# PIC32MZ.net
KiCad netlist of a schematic drawn in Altium Designer
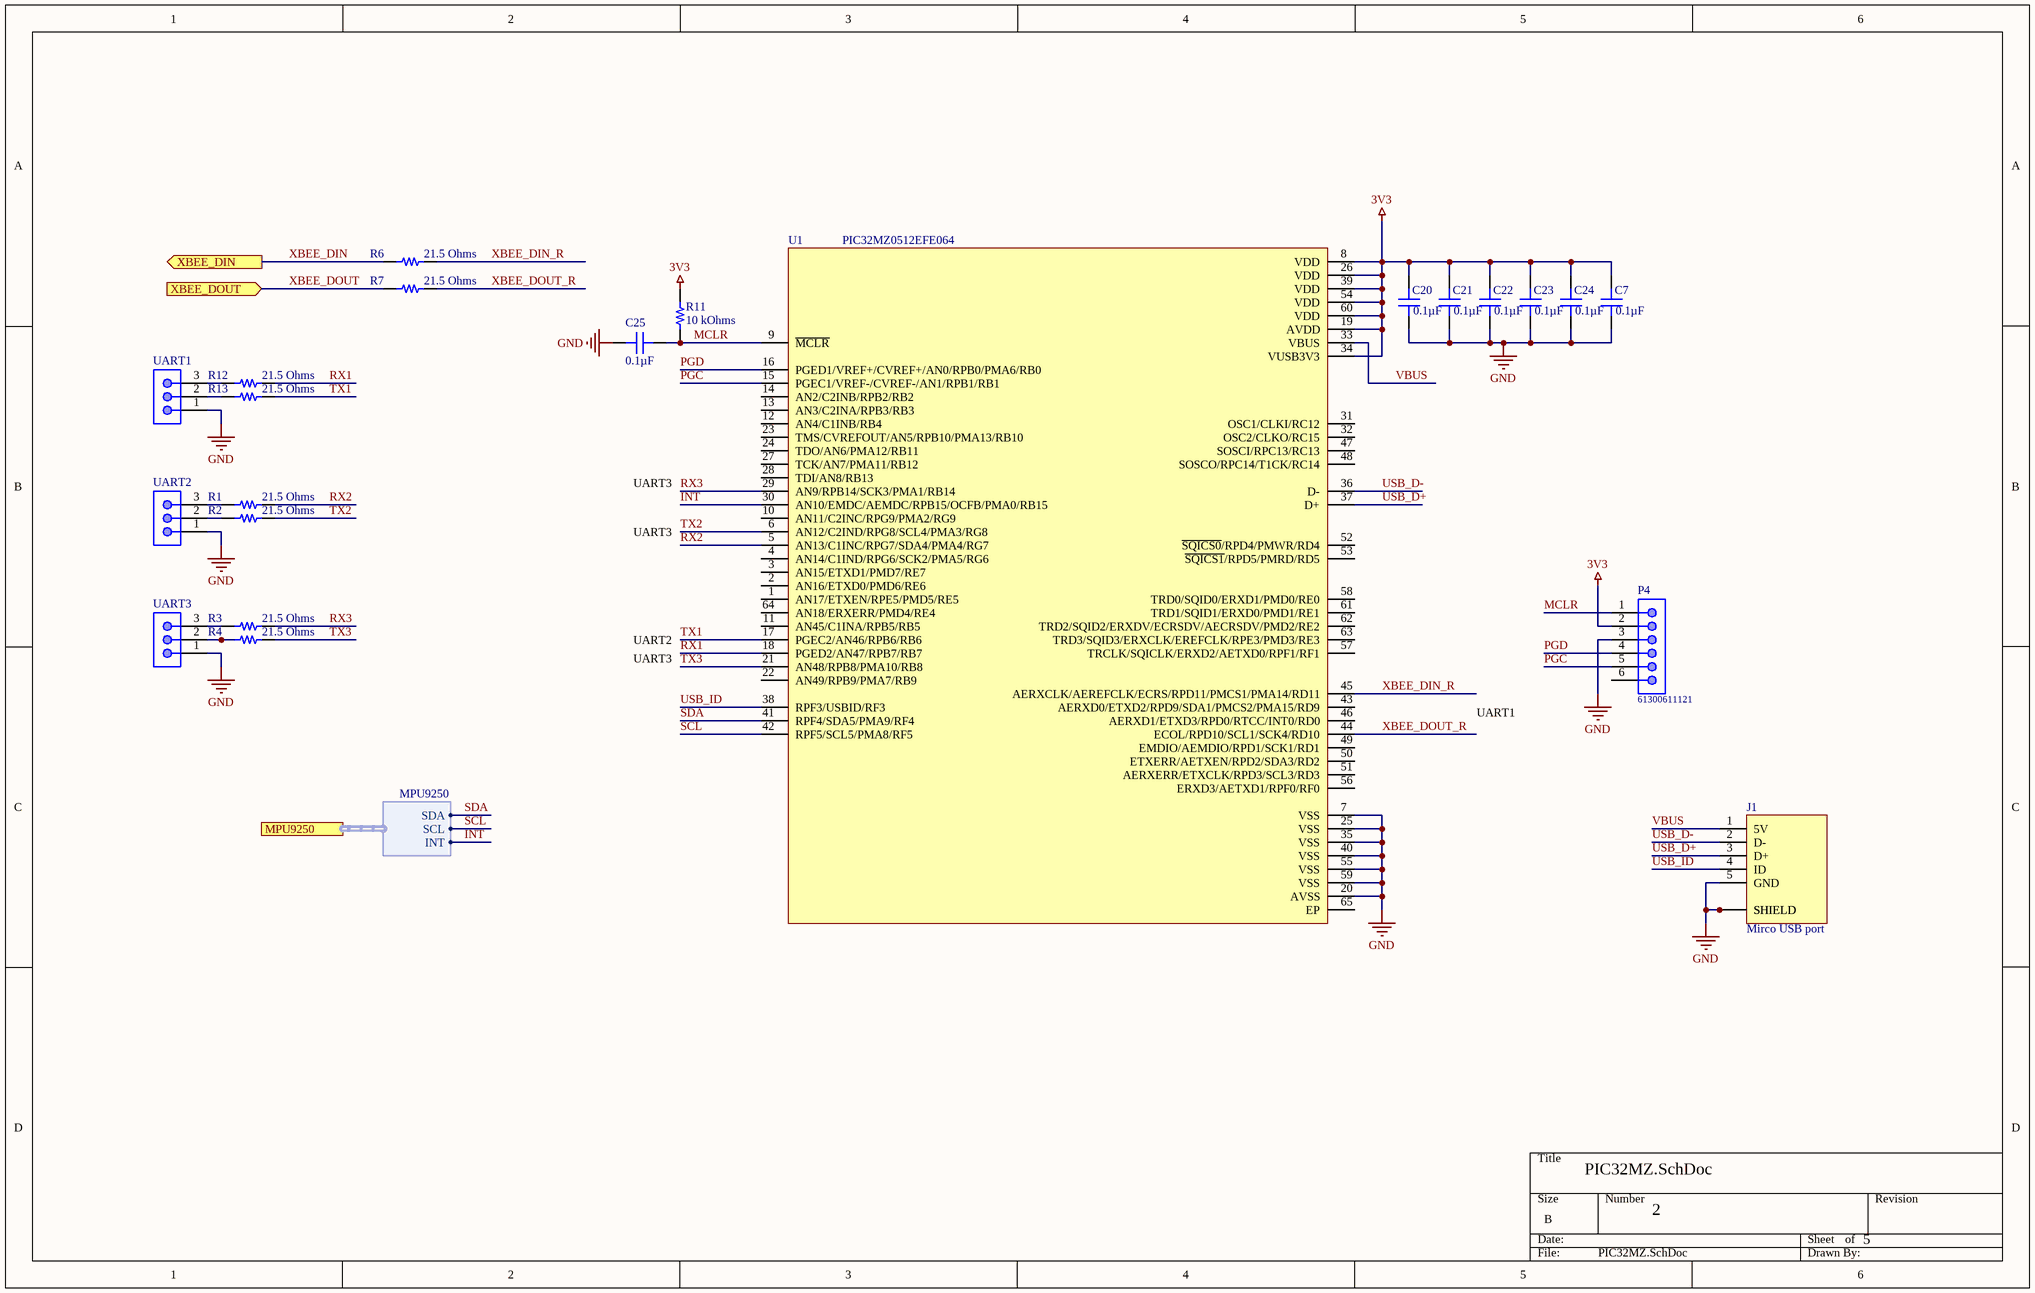
[diagram p0: PIC32MZ.SchDoc]

(export (version "E")
  (design (tool "Eeschema 10.0.6"))
  (components
    (comp (ref "C7")
      (value "0.1µF")
      (footprint "CAP 0603_1608")
      (description "CAP CER 0.1UF 100V 0603 EPOXY")
      (fields
        (field (name "PART NUMBER") "GCG188R92A104KA03D")
        (field (name "MANUFACTURER") "Murata Electronics")
      )
      (libsource (lib "Celestial Altium Library - altium_library") (part "Capacitor"))
    )
    (comp (ref "C20")
      (value "0.1µF")
      (footprint "CAP 0603_1608")
      (description "CAP CER 0.1UF 100V 0603 EPOXY")
      (fields
        (field (name "PART NUMBER") "GCG188R92A104KA03D")
        (field (name "MANUFACTURER") "Murata Electronics")
      )
      (libsource (lib "Celestial Altium Library - altium_library") (part "Capacitor"))
    )
    (comp (ref "C21")
      (value "0.1µF")
      (footprint "CAP 0603_1608")
      (description "CAP CER 0.1UF 100V 0603 EPOXY")
      (fields
        (field (name "PART NUMBER") "GCG188R92A104KA03D")
        (field (name "MANUFACTURER") "Murata Electronics")
      )
      (libsource (lib "Celestial Altium Library - altium_library") (part "Capacitor"))
    )
    (comp (ref "C22")
      (value "0.1µF")
      (footprint "CAP 0603_1608")
      (description "CAP CER 0.1UF 100V 0603 EPOXY")
      (fields
        (field (name "PART NUMBER") "GCG188R92A104KA03D")
        (field (name "MANUFACTURER") "Murata Electronics")
      )
      (libsource (lib "Celestial Altium Library - altium_library") (part "Capacitor"))
    )
    (comp (ref "C23")
      (value "0.1µF")
      (footprint "CAP 0603_1608")
      (description "CAP CER 0.1UF 100V 0603 EPOXY")
      (fields
        (field (name "PART NUMBER") "GCG188R92A104KA03D")
        (field (name "MANUFACTURER") "Murata Electronics")
      )
      (libsource (lib "Celestial Altium Library - altium_library") (part "Capacitor"))
    )
    (comp (ref "C24")
      (value "0.1µF")
      (footprint "CAP 0603_1608")
      (description "CAP CER 0.1UF 100V 0603 EPOXY")
      (fields
        (field (name "PART NUMBER") "GCG188R92A104KA03D")
        (field (name "MANUFACTURER") "Murata Electronics")
      )
      (libsource (lib "Celestial Altium Library - altium_library") (part "Capacitor"))
    )
    (comp (ref "C25")
      (value "0.1µF")
      (footprint "CAP 0603_1608")
      (description "CAP CER 0.1UF 100V 0603 EPOXY")
      (fields
        (field (name "PART NUMBER") "GCG188R92A104KA03D")
        (field (name "MANUFACTURER") "Murata Electronics")
      )
      (libsource (lib "Celestial Altium Library - altium_library") (part "Capacitor"))
    )
    (comp (ref "J1")
      (value "Mirco USB port")
      (footprint "AMPHENOL_10118194-0001LF")
      (description "USB - micro B USB 2.0 Receptacle Connector 5 Position Surface Mount, Right Angle; Through Hole")
      (fields (field (name "MF") "Amphenol ICC") (field (name "MP") "10118194-0001LF"))
      (libsource (lib "IC") (part "10118194-0001LF"))
    )
    (comp (ref "P4")
      (value "61300611121")
      (footprint "61300611121")
      (description "WR-PHD Pin Header, THT, pitch 2.54mm, Single Row, Vertical, 6p")
      (fields (field (name "MANUFACTURER") "Wurth Elektronik"))
      (libsource (lib "Altium_WR-PHD") (part "61300611121"))
    )
    (comp (ref "R1")
      (value "21.5 Ohms")
      (footprint "RES 0603_1608")
      (description "RES SMD 21.5 OHM 1% 1/10W 0603")
      (fields
        (field (name "PART NUMBER") "ERJ-3EKF21R5V")
        (field (name "MANUFACTURER") "Panasonic Electronic Components")
      )
      (libsource (lib "Celestial Altium Library - altium_library") (part "Resistor"))
    )
    (comp (ref "R2")
      (value "21.5 Ohms")
      (footprint "RES 0603_1608")
      (description "RES SMD 21.5 OHM 1% 1/10W 0603")
      (fields
        (field (name "PART NUMBER") "ERJ-3EKF21R5V")
        (field (name "MANUFACTURER") "Panasonic Electronic Components")
      )
      (libsource (lib "Celestial Altium Library - altium_library") (part "Resistor"))
    )
    (comp (ref "R3")
      (value "21.5 Ohms")
      (footprint "RES 0603_1608")
      (description "RES SMD 21.5 OHM 1% 1/10W 0603")
      (fields
        (field (name "PART NUMBER") "ERJ-3EKF21R5V")
        (field (name "MANUFACTURER") "Panasonic Electronic Components")
      )
      (libsource (lib "Celestial Altium Library - altium_library") (part "Resistor"))
    )
    (comp (ref "R4")
      (value "21.5 Ohms")
      (footprint "RES 0603_1608")
      (description "RES SMD 21.5 OHM 1% 1/10W 0603")
      (fields
        (field (name "PART NUMBER") "ERJ-3EKF21R5V")
        (field (name "MANUFACTURER") "Panasonic Electronic Components")
      )
      (libsource (lib "Celestial Altium Library - altium_library") (part "Resistor"))
    )
    (comp (ref "R6")
      (value "21.5 Ohms")
      (footprint "RES 0603_1608")
      (description "RES SMD 21.5 OHM 1% 1/10W 0603")
      (fields
        (field (name "PART NUMBER") "ERJ-3EKF21R5V")
        (field (name "MANUFACTURER") "Panasonic Electronic Components")
      )
      (libsource (lib "Celestial Altium Library - altium_library") (part "Resistor"))
    )
    (comp (ref "R7")
      (value "21.5 Ohms")
      (footprint "RES 0603_1608")
      (description "RES SMD 21.5 OHM 1% 1/10W 0603")
      (fields
        (field (name "PART NUMBER") "ERJ-3EKF21R5V")
        (field (name "MANUFACTURER") "Panasonic Electronic Components")
      )
      (libsource (lib "Celestial Altium Library - altium_library") (part "Resistor"))
    )
    (comp (ref "R11")
      (value "10 kOhms")
      (footprint "RES 0603_1608")
      (description "RES 10K OHM 0.1% 1/16W 0603")
      (fields
        (field (name "PART NUMBER") "RNCS0603BKE10K0")
        (field (name "MANUFACTURER") "Stackpole Electronics Inc")
      )
      (libsource (lib "Celestial Altium Library - altium_library") (part "Resistor"))
    )
    (comp (ref "R12")
      (value "21.5 Ohms")
      (footprint "RES 0603_1608")
      (description "RES SMD 21.5 OHM 1% 1/10W 0603")
      (fields
        (field (name "PART NUMBER") "ERJ-3EKF21R5V")
        (field (name "MANUFACTURER") "Panasonic Electronic Components")
      )
      (libsource (lib "Celestial Altium Library - altium_library") (part "Resistor"))
    )
    (comp (ref "R13")
      (value "21.5 Ohms")
      (footprint "RES 0603_1608")
      (description "RES SMD 21.5 OHM 1% 1/10W 0603")
      (fields
        (field (name "PART NUMBER") "ERJ-3EKF21R5V")
        (field (name "MANUFACTURER") "Panasonic Electronic Components")
      )
      (libsource (lib "Celestial Altium Library - altium_library") (part "Resistor"))
    )
    (comp (ref "U1")
      (value "PIC32MZ0512EFE064")
      (footprint "QFN50P900X900X100-65N")
      (description "32-bit Microcontrollers - MCU 32-BIT MCU 512KB FL 128KB RAM, No Crypto")
      (fields (field (name "MF") "Microchip") (field (name "MP") "PIC32MZ2048EFG064T-I/PT"))
      (libsource (lib "IC") (part "PIC32MZ0512EFE064-I/PT"))
    )
    (comp (ref "UART1")
      (value "3 pin 2mm JST Male")
      (footprint "3pin - 2mm header")
      (libsource (lib "IC") (part "3 pin 2mm JST Male"))
    )
    (comp (ref "UART2")
      (value "3 pin 2mm JST Male")
      (footprint "3pin - 2mm header")
      (libsource (lib "IC") (part "3 pin 2mm JST Male"))
    )
    (comp (ref "UART3")
      (value "3 pin 2mm JST Male")
      (footprint "3pin - 2mm header")
      (libsource (lib "IC") (part "3 pin 2mm JST Male"))
    )
  )
  (nets
    (net (code "2") (name "/INT") (class "Default")
      (node (ref "U1") (pin "30") (pinfunction "AN10/EMDC/AEMDC/RPB15/OCFB/PMA0/RB15_30") (pintype "passive"))
    )
    (net (code "3") (name "/MCLR") (class "Default")
      (node (ref "C25") (pin "1") (pinfunction "1_1") (pintype "passive"))
      (node (ref "P4") (pin "1") (pinfunction "1_1") (pintype "passive"))
      (node (ref "R11") (pin "1") (pinfunction "1_1") (pintype "passive"))
      (node (ref "U1") (pin "9") (pinfunction "~{MCLR}_9") (pintype "passive"))
    )
    (net (code "4") (name "/PGC") (class "Default")
      (node (ref "P4") (pin "5") (pinfunction "5_5") (pintype "passive"))
      (node (ref "U1") (pin "15") (pinfunction "PGEC1/VREF-/CVREF-/AN1/RPB1/RB1_15") (pintype "passive"))
    )
    (net (code "5") (name "/PGD") (class "Default")
      (node (ref "P4") (pin "4") (pinfunction "4_4") (pintype "passive"))
      (node (ref "U1") (pin "16") (pinfunction "PGED1/VREF+/CVREF+/AN0/RPB0/PMA6/RB0_16") (pintype "passive"))
    )
    (net (code "6") (name "/RX1") (class "Default")
      (node (ref "R12") (pin "2") (pinfunction "2_2") (pintype "passive"))
      (node (ref "U1") (pin "18") (pinfunction "PGED2/AN47/RPB7/RB7_18") (pintype "passive"))
    )
    (net (code "7") (name "/RX2") (class "Default")
      (node (ref "R1") (pin "2") (pinfunction "2_2") (pintype "passive"))
      (node (ref "U1") (pin "5") (pinfunction "AN13/C1INC/RPG7/SDA4/PMA4/RG7_5") (pintype "passive"))
    )
    (net (code "8") (name "/RX3") (class "Default")
      (node (ref "R3") (pin "2") (pinfunction "2_2") (pintype "passive"))
      (node (ref "U1") (pin "29") (pinfunction "AN9/RPB14/SCK3/PMA1/RB14_29") (pintype "passive"))
    )
    (net (code "9") (name "/SCL") (class "Default")
      (node (ref "U1") (pin "42") (pinfunction "RPF5/SCL5/PMA8/RF5_42") (pintype "passive"))
    )
    (net (code "10") (name "/SDA") (class "Default")
      (node (ref "U1") (pin "41") (pinfunction "RPF4/SDA5/PMA9/RF4_41") (pintype "passive"))
    )
    (net (code "11") (name "/TX1") (class "Default")
      (node (ref "R13") (pin "2") (pinfunction "2_2") (pintype "passive"))
      (node (ref "U1") (pin "17") (pinfunction "PGEC2/AN46/RPB6/RB6_17") (pintype "passive"))
    )
    (net (code "12") (name "/TX2") (class "Default")
      (node (ref "R2") (pin "2") (pinfunction "2_2") (pintype "passive"))
      (node (ref "U1") (pin "6") (pinfunction "AN12/C2IND/RPG8/SCL4/PMA3/RG8_6") (pintype "passive"))
    )
    (net (code "13") (name "/TX3") (class "Default")
      (node (ref "R4") (pin "2") (pinfunction "2_2") (pintype "passive"))
      (node (ref "U1") (pin "21") (pinfunction "AN48/RPB8/PMA10/RB8_21") (pintype "passive"))
    )
    (net (code "14") (name "/USB_D+") (class "Default")
      (node (ref "J1") (pin "3") (pinfunction "D+_3") (pintype "passive"))
      (node (ref "U1") (pin "37") (pinfunction "D+_37") (pintype "passive"))
    )
    (net (code "15") (name "/USB_D-") (class "Default")
      (node (ref "J1") (pin "2") (pinfunction "D-_2") (pintype "passive"))
      (node (ref "U1") (pin "36") (pinfunction "D-_36") (pintype "passive"))
    )
    (net (code "16") (name "/USB_ID") (class "Default")
      (node (ref "J1") (pin "4") (pinfunction "ID_4") (pintype "passive"))
      (node (ref "U1") (pin "38") (pinfunction "RPF3/USBID/RF3_38") (pintype "passive"))
    )
    (net (code "17") (name "/VBUS") (class "Default")
      (node (ref "J1") (pin "1") (pinfunction "5V_1") (pintype "passive"))
      (node (ref "U1") (pin "33") (pinfunction "VBUS_33") (pintype "power_in"))
    )
    (net (code "18") (name "/XBEE_DIN") (class "Default")
      (node (ref "R6") (pin "1") (pinfunction "1_1") (pintype "passive"))
    )
    (net (code "19") (name "/XBEE_DIN_R") (class "Default")
      (node (ref "R6") (pin "2") (pinfunction "2_2") (pintype "passive"))
      (node (ref "U1") (pin "45") (pinfunction "AERXCLK/AEREFCLK/ECRS/RPD11/PMCS1/PMA14/RD11_45") (pintype "passive"))
    )
    (net (code "20") (name "/XBEE_DOUT") (class "Default")
      (node (ref "R7") (pin "1") (pinfunction "1_1") (pintype "passive"))
    )
    (net (code "21") (name "/XBEE_DOUT_R") (class "Default")
      (node (ref "R7") (pin "2") (pinfunction "2_2") (pintype "passive"))
      (node (ref "U1") (pin "44") (pinfunction "ECOL/RPD10/SCL1/SCK4/RD10_44") (pintype "passive"))
    )
    (net (code "23") (name "3V3") (class "Default")
      (node (ref "C20") (pin "1") (pinfunction "1_1") (pintype "passive"))
      (node (ref "C21") (pin "1") (pinfunction "1_1") (pintype "passive"))
      (node (ref "C22") (pin "1") (pinfunction "1_1") (pintype "passive"))
      (node (ref "C23") (pin "1") (pinfunction "1_1") (pintype "passive"))
      (node (ref "C24") (pin "1") (pinfunction "1_1") (pintype "passive"))
      (node (ref "C7") (pin "1") (pinfunction "1_1") (pintype "passive"))
      (node (ref "P4") (pin "2") (pinfunction "2_2") (pintype "passive"))
      (node (ref "R11") (pin "2") (pinfunction "2_2") (pintype "passive"))
      (node (ref "U1") (pin "19") (pinfunction "AVDD_19") (pintype "power_in"))
      (node (ref "U1") (pin "26") (pinfunction "VDD_26") (pintype "power_in"))
      (node (ref "U1") (pin "34") (pinfunction "VUSB3V3_34") (pintype "power_in"))
      (node (ref "U1") (pin "39") (pinfunction "VDD_39") (pintype "power_in"))
      (node (ref "U1") (pin "54") (pinfunction "VDD_54") (pintype "power_in"))
      (node (ref "U1") (pin "60") (pinfunction "VDD_60") (pintype "power_in"))
      (node (ref "U1") (pin "8") (pinfunction "VDD_8") (pintype "power_in"))
    )
    (net (code "24") (name "GND") (class "Default")
      (node (ref "C20") (pin "2") (pinfunction "2_2") (pintype "passive"))
      (node (ref "C21") (pin "2") (pinfunction "2_2") (pintype "passive"))
      (node (ref "C22") (pin "2") (pinfunction "2_2") (pintype "passive"))
      (node (ref "C23") (pin "2") (pinfunction "2_2") (pintype "passive"))
      (node (ref "C24") (pin "2") (pinfunction "2_2") (pintype "passive"))
      (node (ref "C25") (pin "2") (pinfunction "2_2") (pintype "passive"))
      (node (ref "C7") (pin "2") (pinfunction "2_2") (pintype "passive"))
      (node (ref "J1") (pin "5") (pinfunction "GND_5") (pintype "passive"))
      (node (ref "J1") (pin "S1") (pinfunction "SHIELD_S1") (pintype "passive"))
      (node (ref "J1") (pin "S2") (pinfunction "SHIELD_S2") (pintype "passive"))
      (node (ref "J1") (pin "S3") (pinfunction "SHIELD_S3") (pintype "passive"))
      (node (ref "J1") (pin "S4") (pinfunction "SHIELD_S4") (pintype "passive"))
      (node (ref "J1") (pin "S5") (pinfunction "SHIELD_S5") (pintype "passive"))
      (node (ref "J1") (pin "S6") (pinfunction "SHIELD_S6") (pintype "passive"))
      (node (ref "P4") (pin "3") (pinfunction "3_3") (pintype "passive"))
      (node (ref "U1") (pin "20") (pinfunction "AVSS_20") (pintype "power_in"))
      (node (ref "U1") (pin "25") (pinfunction "VSS_25") (pintype "power_in"))
      (node (ref "U1") (pin "35") (pinfunction "VSS_35") (pintype "power_in"))
      (node (ref "U1") (pin "40") (pinfunction "VSS_40") (pintype "power_in"))
      (node (ref "U1") (pin "55") (pinfunction "VSS_55") (pintype "power_in"))
      (node (ref "U1") (pin "59") (pinfunction "VSS_59") (pintype "power_in"))
      (node (ref "U1") (pin "7") (pinfunction "VSS_7") (pintype "power_in"))
      (node (ref "UART1") (pin "1") (pinfunction "1_1") (pintype "passive"))
      (node (ref "UART2") (pin "1") (pinfunction "1_1") (pintype "passive"))
      (node (ref "UART3") (pin "1") (pinfunction "1_1") (pintype "passive"))
    )
    (net (code "25") (name "Net-(R1-Pad1)") (class "Default")
      (node (ref "R1") (pin "1") (pinfunction "1_1") (pintype "passive"))
      (node (ref "UART2") (pin "3") (pinfunction "3_3") (pintype "passive"))
    )
    (net (code "26") (name "Net-(R2-Pad1)") (class "Default")
      (node (ref "R2") (pin "1") (pinfunction "1_1") (pintype "passive"))
      (node (ref "UART2") (pin "2") (pinfunction "2_2") (pintype "passive"))
    )
    (net (code "27") (name "Net-(R3-Pad1)") (class "Default")
      (node (ref "R3") (pin "1") (pinfunction "1_1") (pintype "passive"))
      (node (ref "UART3") (pin "3") (pinfunction "3_3") (pintype "passive"))
    )
    (net (code "28") (name "Net-(R4-Pad1)") (class "Default")
      (node (ref "R4") (pin "1") (pinfunction "1_1") (pintype "passive"))
      (node (ref "UART3") (pin "2") (pinfunction "2_2") (pintype "passive"))
    )
    (net (code "29") (name "Net-(R12-Pad1)") (class "Default")
      (node (ref "R12") (pin "1") (pinfunction "1_1") (pintype "passive"))
      (node (ref "UART1") (pin "3") (pinfunction "3_3") (pintype "passive"))
    )
    (net (code "30") (name "Net-(R13-Pad1)") (class "Default")
      (node (ref "R13") (pin "1") (pinfunction "1_1") (pintype "passive"))
      (node (ref "UART1") (pin "2") (pinfunction "2_2") (pintype "passive"))
    )
    (net (code "31") (name "unconnected-(P4-Pad6)") (class "Default")
      (node (ref "P4") (pin "6") (pinfunction "6_6") (pintype "passive"))
    )
    (net (code "32") (name "unconnected-(U1-AERXD0{slash}ETXD2{slash}RPD9{slash}SDA1{slash}PMCS2{slash}PMA15{slash}RD9-Pad43)") (class "Default")
      (node (ref "U1") (pin "43") (pinfunction "AERXD0/ETXD2/RPD9/SDA1/PMCS2/PMA15/RD9_43") (pintype "passive"))
    )
    (net (code "33") (name "unconnected-(U1-AERXD1{slash}ETXD3{slash}RPD0{slash}RTCC{slash}INT0{slash}RD0-Pad46)") (class "Default")
      (node (ref "U1") (pin "46") (pinfunction "AERXD1/ETXD3/RPD0/RTCC/INT0/RD0_46") (pintype "passive"))
    )
    (net (code "34") (name "unconnected-(U1-AERXERR{slash}ETXCLK{slash}RPD3{slash}SCL3{slash}RD3-Pad51)") (class "Default")
      (node (ref "U1") (pin "51") (pinfunction "AERXERR/ETXCLK/RPD3/SCL3/RD3_51") (pintype "passive"))
    )
    (net (code "35") (name "unconnected-(U1-AN2{slash}C2INB{slash}RPB2{slash}RB2-Pad14)") (class "Default")
      (node (ref "U1") (pin "14") (pinfunction "AN2/C2INB/RPB2/RB2_14") (pintype "passive"))
    )
    (net (code "36") (name "unconnected-(U1-AN3{slash}C2INA{slash}RPB3{slash}RB3-Pad13)") (class "Default")
      (node (ref "U1") (pin "13") (pinfunction "AN3/C2INA/RPB3/RB3_13") (pintype "passive"))
    )
    (net (code "37") (name "unconnected-(U1-AN4{slash}C1INB{slash}RB4-Pad12)") (class "Default")
      (node (ref "U1") (pin "12") (pinfunction "AN4/C1INB/RB4_12") (pintype "passive"))
    )
    (net (code "38") (name "unconnected-(U1-AN11{slash}C2INC{slash}RPG9{slash}PMA2{slash}RG9-Pad10)") (class "Default")
      (node (ref "U1") (pin "10") (pinfunction "AN11/C2INC/RPG9/PMA2/RG9_10") (pintype "passive"))
    )
    (net (code "39") (name "unconnected-(U1-AN14{slash}C1IND{slash}RPG6{slash}SCK2{slash}PMA5{slash}RG6-Pad4)") (class "Default")
      (node (ref "U1") (pin "4") (pinfunction "AN14/C1IND/RPG6/SCK2/PMA5/RG6_4") (pintype "passive"))
    )
    (net (code "40") (name "unconnected-(U1-AN15{slash}ETXD1{slash}PMD7{slash}RE7-Pad3)") (class "Default")
      (node (ref "U1") (pin "3") (pinfunction "AN15/ETXD1/PMD7/RE7_3") (pintype "passive"))
    )
    (net (code "41") (name "unconnected-(U1-AN16{slash}ETXD0{slash}PMD6{slash}RE6-Pad2)") (class "Default")
      (node (ref "U1") (pin "2") (pinfunction "AN16/ETXD0/PMD6/RE6_2") (pintype "passive"))
    )
    (net (code "42") (name "unconnected-(U1-AN17{slash}ETXEN{slash}RPE5{slash}PMD5{slash}RE5-Pad1)") (class "Default")
      (node (ref "U1") (pin "1") (pinfunction "AN17/ETXEN/RPE5/PMD5/RE5_1") (pintype "passive"))
    )
    (net (code "43") (name "unconnected-(U1-AN18{slash}ERXERR{slash}PMD4{slash}RE4-Pad64)") (class "Default")
      (node (ref "U1") (pin "64") (pinfunction "AN18/ERXERR/PMD4/RE4_64") (pintype "passive"))
    )
    (net (code "44") (name "unconnected-(U1-AN45{slash}C1INA{slash}RPB5{slash}RB5-Pad11)") (class "Default")
      (node (ref "U1") (pin "11") (pinfunction "AN45/C1INA/RPB5/RB5_11") (pintype "passive"))
    )
    (net (code "45") (name "unconnected-(U1-AN49{slash}RPB9{slash}PMA7{slash}RB9-Pad22)") (class "Default")
      (node (ref "U1") (pin "22") (pinfunction "AN49/RPB9/PMA7/RB9_22") (pintype "passive"))
    )
    (net (code "46") (name "unconnected-(U1-EMDIO{slash}AEMDIO{slash}RPD1{slash}SCK1{slash}RD1-Pad49)") (class "Default")
      (node (ref "U1") (pin "49") (pinfunction "EMDIO/AEMDIO/RPD1/SCK1/RD1_49") (pintype "passive"))
    )
    (net (code "47") (name "unconnected-(U1-EP-Pad65)") (class "Default")
      (node (ref "U1") (pin "65") (pinfunction "EP_65") (pintype "power_in"))
    )
    (net (code "48") (name "unconnected-(U1-ERXD3{slash}AETXD1{slash}RPF0{slash}RF0-Pad56)") (class "Default")
      (node (ref "U1") (pin "56") (pinfunction "ERXD3/AETXD1/RPF0/RF0_56") (pintype "passive"))
    )
    (net (code "49") (name "unconnected-(U1-ETXERR{slash}AETXEN{slash}RPD2{slash}SDA3{slash}RD2-Pad50)") (class "Default")
      (node (ref "U1") (pin "50") (pinfunction "ETXERR/AETXEN/RPD2/SDA3/RD2_50") (pintype "passive"))
    )
    (net (code "50") (name "unconnected-(U1-OSC1{slash}CLKI{slash}RC12-Pad31)") (class "Default")
      (node (ref "U1") (pin "31") (pinfunction "OSC1/CLKI/RC12_31") (pintype "passive"))
    )
    (net (code "51") (name "unconnected-(U1-OSC2{slash}CLKO{slash}RC15-Pad32)") (class "Default")
      (node (ref "U1") (pin "32") (pinfunction "OSC2/CLKO/RC15_32") (pintype "passive"))
    )
    (net (code "52") (name "unconnected-(U1-SOSCI{slash}RPC13{slash}RC13-Pad47)") (class "Default")
      (node (ref "U1") (pin "47") (pinfunction "SOSCI/RPC13/RC13_47") (pintype "passive"))
    )
    (net (code "53") (name "unconnected-(U1-SOSCO{slash}RPC14{slash}T1CK{slash}RC14-Pad48)") (class "Default")
      (node (ref "U1") (pin "48") (pinfunction "SOSCO/RPC14/T1CK/RC14_48") (pintype "passive"))
    )
    (net (code "54") (name "unconnected-(U1-TCK{slash}AN7{slash}PMA11{slash}RB12-Pad27)") (class "Default")
      (node (ref "U1") (pin "27") (pinfunction "TCK/AN7/PMA11/RB12_27") (pintype "passive"))
    )
    (net (code "55") (name "unconnected-(U1-TDI{slash}AN8{slash}RB13-Pad28)") (class "Default")
      (node (ref "U1") (pin "28") (pinfunction "TDI/AN8/RB13_28") (pintype "passive"))
    )
    (net (code "56") (name "unconnected-(U1-TDO{slash}AN6{slash}PMA12{slash}RB11-Pad24)") (class "Default")
      (node (ref "U1") (pin "24") (pinfunction "TDO/AN6/PMA12/RB11_24") (pintype "passive"))
    )
    (net (code "57") (name "unconnected-(U1-TMS{slash}CVREFOUT{slash}AN5{slash}RPB10{slash}PMA13{slash}RB10-Pad23)") (class "Default")
      (node (ref "U1") (pin "23") (pinfunction "TMS/CVREFOUT/AN5/RPB10/PMA13/RB10_23") (pintype "passive"))
    )
    (net (code "58") (name "unconnected-(U1-TRCLK{slash}SQICLK{slash}ERXD2{slash}AETXD0{slash}RPF1{slash}RF1-Pad57)") (class "Default")
      (node (ref "U1") (pin "57") (pinfunction "TRCLK/SQICLK/ERXD2/AETXD0/RPF1/RF1_57") (pintype "passive"))
    )
    (net (code "59") (name "unconnected-(U1-TRD0{slash}SQID0{slash}ERXD1{slash}PMD0{slash}RE0-Pad58)") (class "Default")
      (node (ref "U1") (pin "58") (pinfunction "TRD0/SQID0/ERXD1/PMD0/RE0_58") (pintype "passive"))
    )
    (net (code "60") (name "unconnected-(U1-TRD1{slash}SQID1{slash}ERXD0{slash}PMD1{slash}RE1-Pad61)") (class "Default")
      (node (ref "U1") (pin "61") (pinfunction "TRD1/SQID1/ERXD0/PMD1/RE1_61") (pintype "passive"))
    )
    (net (code "61") (name "unconnected-(U1-TRD2{slash}SQID2{slash}ERXDV{slash}ECRSDV{slash}AECRSDV{slash}PMD2{slash}RE2-Pad62)") (class "Default")
      (node (ref "U1") (pin "62") (pinfunction "TRD2/SQID2/ERXDV/ECRSDV/AECRSDV/PMD2/RE2_62") (pintype "passive"))
    )
    (net (code "62") (name "unconnected-(U1-TRD3{slash}SQID3{slash}ERXCLK{slash}EREFCLK{slash}RPE3{slash}PMD3{slash}RE3-Pad63)") (class "Default")
      (node (ref "U1") (pin "63") (pinfunction "TRD3/SQID3/ERXCLK/EREFCLK/RPE3/PMD3/RE3_63") (pintype "passive"))
    )
    (net (code "63") (name "unconnected-(U1-~{SQICS0}{slash}RPD4{slash}PMWR{slash}RD4-Pad52)") (class "Default")
      (node (ref "U1") (pin "52") (pinfunction "~{SQICS0}/RPD4/PMWR/RD4_52") (pintype "passive"))
    )
    (net (code "64") (name "unconnected-(U1-~{SQICS1}{slash}RPD5{slash}PMRD{slash}RD5-Pad53)") (class "Default")
      (node (ref "U1") (pin "53") (pinfunction "~{SQICS1}/RPD5/PMRD/RD5_53") (pintype "passive"))
    )
  )
)
